# fryza-mied.net
KiCad netlist of a schematic drawn in EAGLE
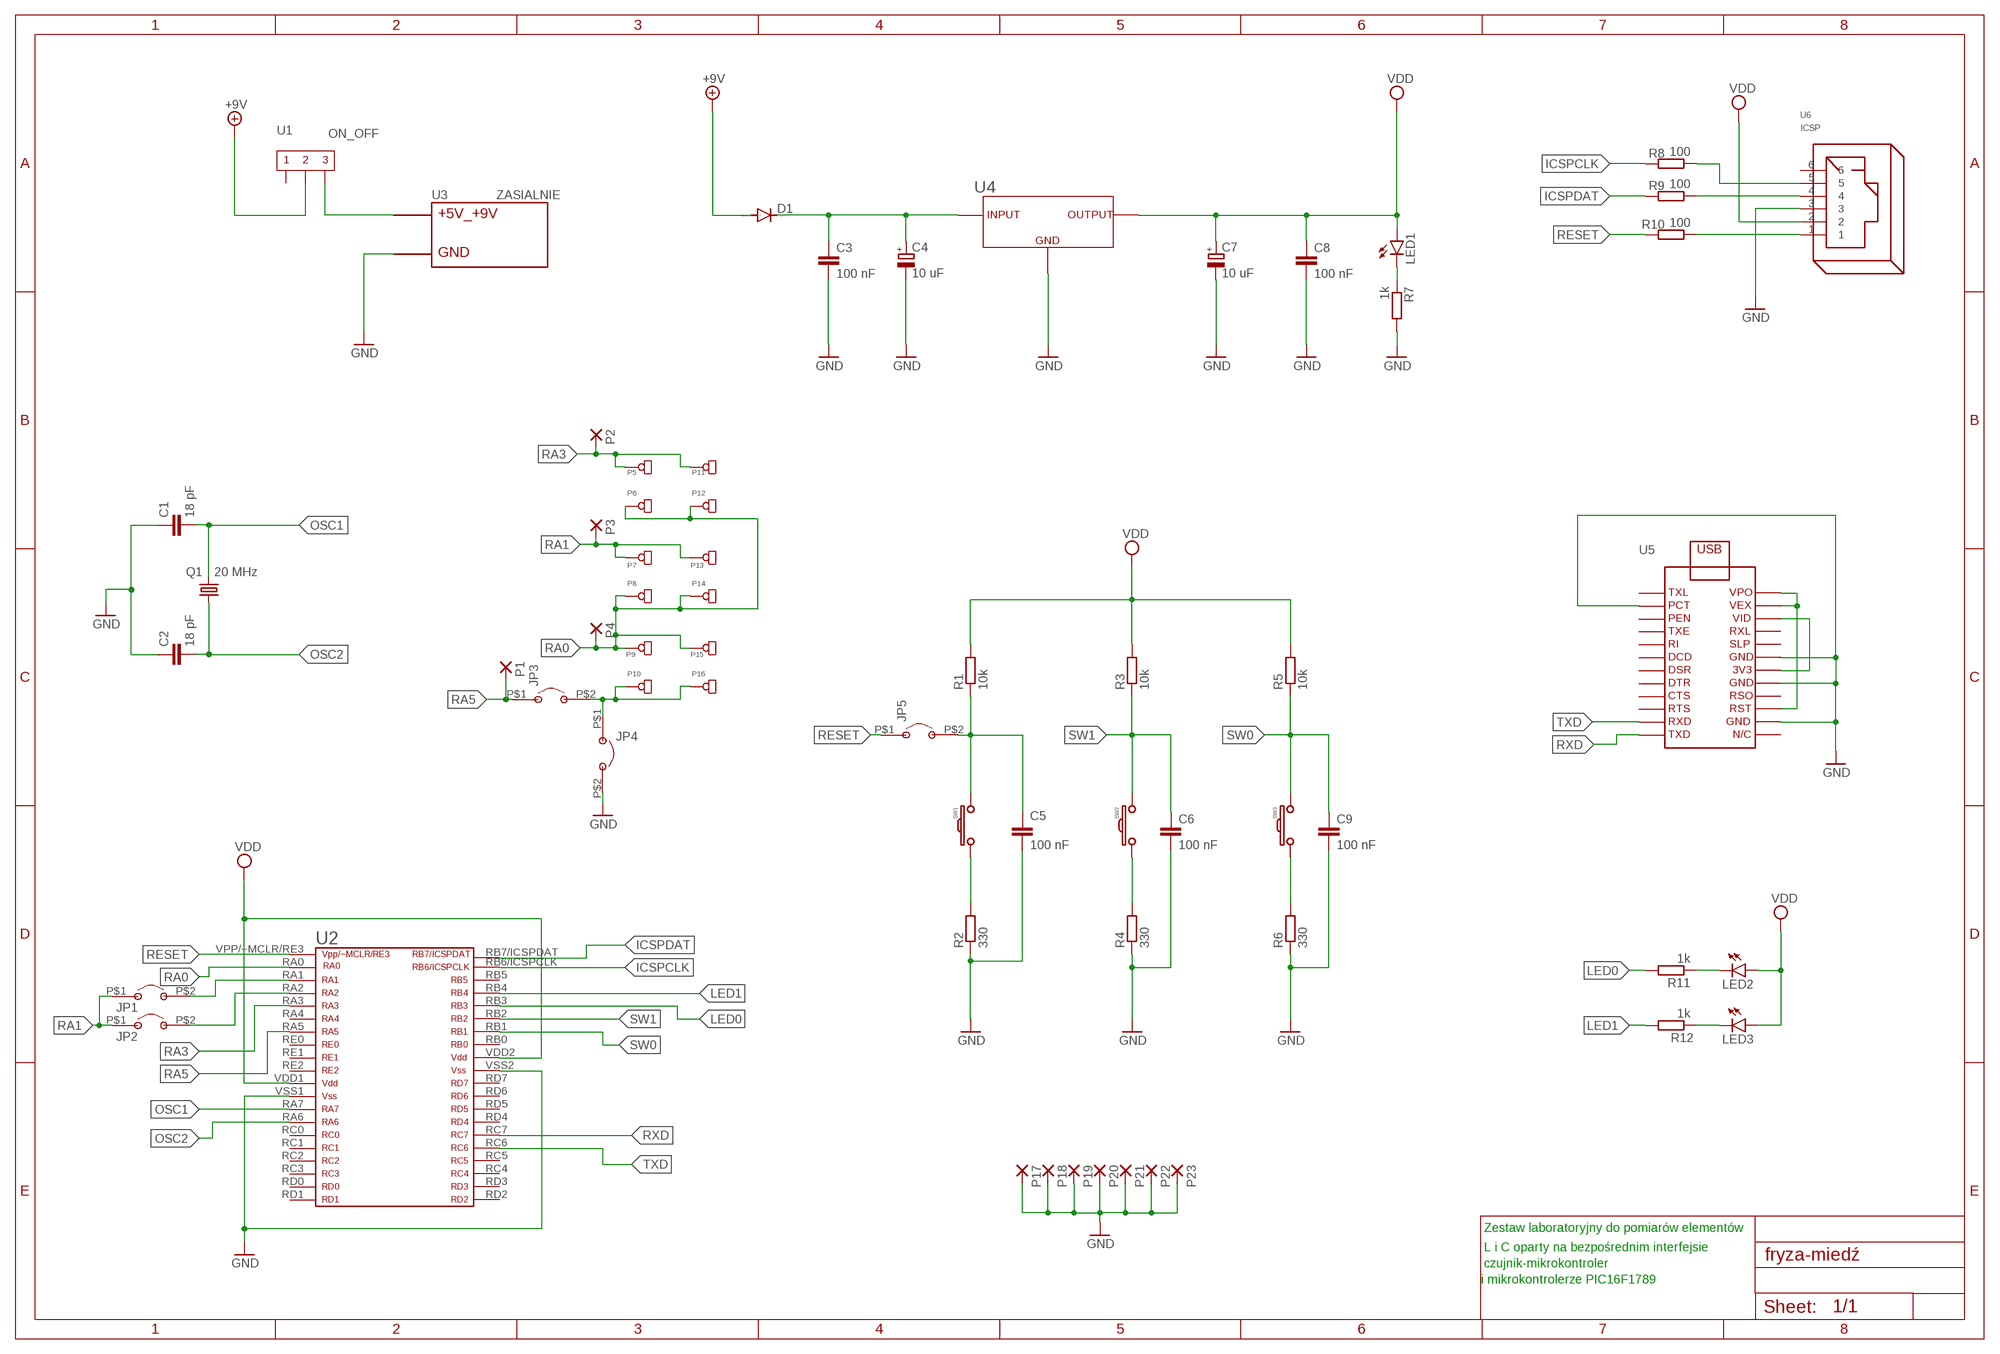
[diagram p0: schematic, sheet 1]

(export (version "E")
  (design (tool "Eeschema 10.0.6"))
  (components
    (comp (ref "C1")
      (value "18 pF")
      (footprint "eagle-import:C050-035X075")
      (libsource (lib "eagle-import") (part "C-EU050-035X075"))
    )
    (comp (ref "C2")
      (value "18 pF")
      (footprint "eagle-import:C050-035X075")
      (libsource (lib "eagle-import") (part "C-EU050-035X075"))
    )
    (comp (ref "C3")
      (value "100 nF")
      (footprint "eagle-import:C050-035X075")
      (libsource (lib "eagle-import") (part "C-EU050-035X075"))
    )
    (comp (ref "C4")
      (value "10 uF")
      (footprint "eagle-import:E2,5-5")
      (libsource (lib "eagle-import") (part "CPOL-EUE2.5-5"))
    )
    (comp (ref "C5")
      (value "100 nF")
      (footprint "eagle-import:C050-035X075")
      (libsource (lib "eagle-import") (part "C-EU050-035X075"))
    )
    (comp (ref "C6")
      (value "100 nF")
      (footprint "eagle-import:C050-035X075")
      (libsource (lib "eagle-import") (part "C-EU050-035X075"))
    )
    (comp (ref "C7")
      (value "10 uF")
      (footprint "eagle-import:E2,5-5")
      (libsource (lib "eagle-import") (part "CPOL-EUE2.5-5"))
    )
    (comp (ref "C8")
      (value "100 nF")
      (footprint "eagle-import:C050-035X075")
      (libsource (lib "eagle-import") (part "C-EU050-035X075"))
    )
    (comp (ref "C9")
      (value "100 nF")
      (footprint "eagle-import:C050-035X075")
      (libsource (lib "eagle-import") (part "C-EU050-035X075"))
    )
    (comp (ref "D1")
      (value "1N4004")
      (footprint "eagle-import:DO41-10")
      (libsource (lib "eagle-import") (part "1N4004"))
    )
    (comp (ref "JP1")
      (value "JUMPER")
      (footprint "eagle-import:JUMPER")
      (libsource (lib "eagle-import") (part "JUMPER"))
    )
    (comp (ref "JP2")
      (value "JUMPER")
      (footprint "eagle-import:JUMPER")
      (libsource (lib "eagle-import") (part "JUMPER"))
    )
    (comp (ref "JP3")
      (value "JUMPER")
      (footprint "eagle-import:JUMPER")
      (libsource (lib "eagle-import") (part "JUMPER"))
    )
    (comp (ref "JP4")
      (value "JUMPER")
      (footprint "eagle-import:JUMPER")
      (libsource (lib "eagle-import") (part "JUMPER"))
    )
    (comp (ref "JP5")
      (value "JUMPER")
      (footprint "eagle-import:JUMPER")
      (libsource (lib "eagle-import") (part "JUMPER"))
    )
    (comp (ref "LED1")
      (value "LED5MM")
      (footprint "eagle-import:LED5MM")
      (libsource (lib "eagle-import") (part "LED5MM"))
    )
    (comp (ref "LED2")
      (value "LED5MM")
      (footprint "eagle-import:LED5MM")
      (libsource (lib "eagle-import") (part "LED5MM"))
    )
    (comp (ref "LED3")
      (value "LED5MM")
      (footprint "eagle-import:LED5MM")
      (libsource (lib "eagle-import") (part "LED5MM"))
    )
    (comp (ref "P1")
      (value "SZPILKA")
      (footprint "eagle-import:CON")
      (libsource (lib "eagle-import") (part "SZPILKA"))
    )
    (comp (ref "P2")
      (value "SZPILKA")
      (footprint "eagle-import:CON")
      (libsource (lib "eagle-import") (part "SZPILKA"))
    )
    (comp (ref "P3")
      (value "SZPILKA")
      (footprint "eagle-import:CON")
      (libsource (lib "eagle-import") (part "SZPILKA"))
    )
    (comp (ref "P4")
      (value "SZPILKA")
      (footprint "eagle-import:CON")
      (libsource (lib "eagle-import") (part "SZPILKA"))
    )
    (comp (ref "P5")
      (value "CON")
      (footprint "eagle-import:CON")
      (libsource (lib "eagle-import") (part "CON"))
    )
    (comp (ref "P6")
      (value "CON")
      (footprint "eagle-import:CON")
      (libsource (lib "eagle-import") (part "CON"))
    )
    (comp (ref "P7")
      (value "CON")
      (footprint "eagle-import:CON")
      (libsource (lib "eagle-import") (part "CON"))
    )
    (comp (ref "P8")
      (value "CON")
      (footprint "eagle-import:CON")
      (libsource (lib "eagle-import") (part "CON"))
    )
    (comp (ref "P9")
      (value "CON")
      (footprint "eagle-import:CON")
      (libsource (lib "eagle-import") (part "CON"))
    )
    (comp (ref "P10")
      (value "CON")
      (footprint "eagle-import:CON")
      (libsource (lib "eagle-import") (part "CON"))
    )
    (comp (ref "P11")
      (value "CON")
      (footprint "eagle-import:CON")
      (libsource (lib "eagle-import") (part "CON"))
    )
    (comp (ref "P12")
      (value "CON")
      (footprint "eagle-import:CON")
      (libsource (lib "eagle-import") (part "CON"))
    )
    (comp (ref "P13")
      (value "CON")
      (footprint "eagle-import:CON")
      (libsource (lib "eagle-import") (part "CON"))
    )
    (comp (ref "P14")
      (value "CON")
      (footprint "eagle-import:CON")
      (libsource (lib "eagle-import") (part "CON"))
    )
    (comp (ref "P15")
      (value "CON")
      (footprint "eagle-import:CON")
      (libsource (lib "eagle-import") (part "CON"))
    )
    (comp (ref "P16")
      (value "CON")
      (footprint "eagle-import:CON")
      (libsource (lib "eagle-import") (part "CON"))
    )
    (comp (ref "P17")
      (value "SZPILKA")
      (footprint "eagle-import:CON")
      (libsource (lib "eagle-import") (part "SZPILKA"))
    )
    (comp (ref "P18")
      (value "SZPILKA")
      (footprint "eagle-import:CON")
      (libsource (lib "eagle-import") (part "SZPILKA"))
    )
    (comp (ref "P19")
      (value "SZPILKA")
      (footprint "eagle-import:CON")
      (libsource (lib "eagle-import") (part "SZPILKA"))
    )
    (comp (ref "P20")
      (value "SZPILKA")
      (footprint "eagle-import:CON")
      (libsource (lib "eagle-import") (part "SZPILKA"))
    )
    (comp (ref "P21")
      (value "SZPILKA")
      (footprint "eagle-import:CON")
      (libsource (lib "eagle-import") (part "SZPILKA"))
    )
    (comp (ref "P22")
      (value "SZPILKA")
      (footprint "eagle-import:CON")
      (libsource (lib "eagle-import") (part "SZPILKA"))
    )
    (comp (ref "P23")
      (value "SZPILKA")
      (footprint "eagle-import:CON")
      (libsource (lib "eagle-import") (part "SZPILKA"))
    )
    (comp (ref "Q1")
      (value "20 MHz")
      (footprint "eagle-import:KWARC")
      (libsource (lib "eagle-import") (part "KWARC"))
    )
    (comp (ref "R1")
      (value "10k")
      (footprint "eagle-import:0207_10")
      (libsource (lib "eagle-import") (part "R-EU_0207/10"))
    )
    (comp (ref "R2")
      (value "330")
      (footprint "eagle-import:0207_10")
      (libsource (lib "eagle-import") (part "R-EU_0207/10"))
    )
    (comp (ref "R3")
      (value "10k")
      (footprint "eagle-import:0207_10")
      (libsource (lib "eagle-import") (part "R-EU_0207/10"))
    )
    (comp (ref "R4")
      (value "330")
      (footprint "eagle-import:0207_10")
      (libsource (lib "eagle-import") (part "R-EU_0207/10"))
    )
    (comp (ref "R5")
      (value "10k")
      (footprint "eagle-import:0207_10")
      (libsource (lib "eagle-import") (part "R-EU_0207/10"))
    )
    (comp (ref "R6")
      (value "330")
      (footprint "eagle-import:0207_10")
      (libsource (lib "eagle-import") (part "R-EU_0207/10"))
    )
    (comp (ref "R7")
      (value "1k")
      (footprint "eagle-import:0207_10")
      (libsource (lib "eagle-import") (part "R-EU_0207/10"))
    )
    (comp (ref "R8")
      (value "100")
      (footprint "eagle-import:0207_10")
      (libsource (lib "eagle-import") (part "R-EU_0207/10"))
    )
    (comp (ref "R9")
      (value "100")
      (footprint "eagle-import:0207_10")
      (libsource (lib "eagle-import") (part "R-EU_0207/10"))
    )
    (comp (ref "R10")
      (value "100")
      (footprint "eagle-import:0207_10")
      (libsource (lib "eagle-import") (part "R-EU_0207/10"))
    )
    (comp (ref "R11")
      (value "1k")
      (footprint "eagle-import:0207_10")
      (libsource (lib "eagle-import") (part "R-EU_0207/10"))
    )
    (comp (ref "R12")
      (value "1k")
      (footprint "eagle-import:0207_10")
      (libsource (lib "eagle-import") (part "R-EU_0207/10"))
    )
    (comp (ref "SW1")
      (value "PUSH_SWITCH")
      (footprint "eagle-import:PUSH_SWITCH")
      (libsource (lib "eagle-import") (part "PUSH_SWITCH"))
    )
    (comp (ref "SW2")
      (value "PUSH_SWITCH")
      (footprint "eagle-import:PUSH_SWITCH")
      (libsource (lib "eagle-import") (part "PUSH_SWITCH"))
    )
    (comp (ref "SW3")
      (value "PUSH_SWITCH")
      (footprint "eagle-import:PUSH_SWITCH")
      (libsource (lib "eagle-import") (part "PUSH_SWITCH"))
    )
    (comp (ref "U1")
      (value "ON_OFF")
      (footprint "eagle-import:WLACZNIK")
      (libsource (lib "eagle-import") (part "WLACZNIK"))
    )
    (comp (ref "U2")
      (value "PIC16F1789")
      (footprint "eagle-import:PIC16F1789")
      (libsource (lib "eagle-import") (part "PIC16F1789"))
    )
    (comp (ref "U3")
      (value "ZASIALNIE")
      (footprint "eagle-import:ZASILANIE_ZLACZE")
      (libsource (lib "eagle-import") (part "ZASILANIE_ZLACZE"))
    )
    (comp (ref "U4")
      (value "LF33CV")
      (footprint "eagle-import:LF33CV")
      (libsource (lib "eagle-import") (part "LF33CV"))
    )
    (comp (ref "U5")
      (value "MMUSB232")
      (footprint "eagle-import:MMUSB232")
      (libsource (lib "eagle-import") (part "MMUSB232"))
    )
    (comp (ref "U6")
      (value "ICSP")
      (footprint "eagle-import:RJ12")
      (libsource (lib "eagle-import") (part "RJ12"))
    )
  )
  (nets
    (net (code "1") (name "+9V") (class "Default")
      (node (ref "D1") (pin "A") (pinfunction "A_A") (pintype "passive"))
      (node (ref "U1") (pin "2") (pinfunction "2_2") (pintype "bidirectional"))
    )
    (net (code "2") (name "GND") (class "Default")
      (node (ref "C1") (pin "1") (pinfunction "1_1") (pintype "passive"))
      (node (ref "C2") (pin "1") (pinfunction "1_1") (pintype "passive"))
      (node (ref "C3") (pin "2") (pinfunction "2_2") (pintype "passive"))
      (node (ref "C4") (pin "-") (pinfunction "-_-") (pintype "passive"))
      (node (ref "C5") (pin "2") (pinfunction "2_2") (pintype "passive"))
      (node (ref "C6") (pin "2") (pinfunction "2_2") (pintype "passive"))
      (node (ref "C7") (pin "-") (pinfunction "-_-") (pintype "passive"))
      (node (ref "C8") (pin "2") (pinfunction "2_2") (pintype "passive"))
      (node (ref "C9") (pin "2") (pinfunction "2_2") (pintype "passive"))
      (node (ref "JP4") (pin "P$2") (pinfunction "P$2_P$2") (pintype "bidirectional"))
      (node (ref "P17") (pin "P$1") (pinfunction "P_P$1") (pintype "passive"))
      (node (ref "P18") (pin "P$1") (pinfunction "P_P$1") (pintype "passive"))
      (node (ref "P19") (pin "P$1") (pinfunction "P_P$1") (pintype "passive"))
      (node (ref "P20") (pin "P$1") (pinfunction "P_P$1") (pintype "passive"))
      (node (ref "P21") (pin "P$1") (pinfunction "P_P$1") (pintype "passive"))
      (node (ref "P22") (pin "P$1") (pinfunction "P_P$1") (pintype "passive"))
      (node (ref "P23") (pin "P$1") (pinfunction "P_P$1") (pintype "passive"))
      (node (ref "R2") (pin "1") (pinfunction "1_1") (pintype "passive"))
      (node (ref "R4") (pin "1") (pinfunction "1_1") (pintype "passive"))
      (node (ref "R6") (pin "1") (pinfunction "1_1") (pintype "passive"))
      (node (ref "R7") (pin "2") (pinfunction "2_2") (pintype "passive"))
      (node (ref "U2") (pin "VSS1") (pinfunction "VSS1_VSS1") (pintype "bidirectional"))
      (node (ref "U2") (pin "VSS2") (pinfunction "VSS2_VSS2") (pintype "bidirectional"))
      (node (ref "U3") (pin "GND1") (pinfunction "GND_GND1") (pintype "bidirectional"))
      (node (ref "U3") (pin "GND2") (pinfunction "GND_GND2") (pintype "bidirectional"))
      (node (ref "U4") (pin "GND") (pinfunction "GND_GND") (pintype "bidirectional"))
      (node (ref "U5") (pin "GND") (pinfunction "GND_GND") (pintype "bidirectional"))
      (node (ref "U5") (pin "GND1") (pinfunction "GND1_GND1") (pintype "bidirectional"))
      (node (ref "U5") (pin "GND2") (pinfunction "GND2_GND2") (pintype "bidirectional"))
      (node (ref "U5") (pin "PCT") (pinfunction "PCT_PCT") (pintype "bidirectional"))
      (node (ref "U6") (pin "3") (pinfunction "3_3") (pintype "bidirectional"))
    )
    (net (code "3") (name "ICSPCLK") (class "Default")
      (node (ref "R8") (pin "2") (pinfunction "2_2") (pintype "passive"))
      (node (ref "U2") (pin "RB6/ICSPCLK") (pinfunction "RB6/ICSPCLK_RB6/ICSPCLK") (pintype "bidirectional"))
    )
    (net (code "4") (name "ICSPDAT") (class "Default")
      (node (ref "R9") (pin "2") (pinfunction "2_2") (pintype "passive"))
      (node (ref "U2") (pin "RB7/ICSPDAT") (pinfunction "RB7/ICSPDAT_RB7/ICSPDAT") (pintype "bidirectional"))
    )
    (net (code "5") (name "LED0") (class "Default")
      (node (ref "R11") (pin "2") (pinfunction "2_2") (pintype "passive"))
      (node (ref "U2") (pin "RB3") (pinfunction "RB3_RB3") (pintype "bidirectional"))
    )
    (net (code "6") (name "LED1") (class "Default")
      (node (ref "R12") (pin "2") (pinfunction "2_2") (pintype "passive"))
      (node (ref "U2") (pin "RB4") (pinfunction "RB4_RB4") (pintype "bidirectional"))
    )
    (net (code "7") (name "Net-(C3-Pad1)") (class "Default")
      (node (ref "C3") (pin "1") (pinfunction "1_1") (pintype "passive"))
      (node (ref "C4") (pin "+") (pinfunction "+_+") (pintype "passive"))
      (node (ref "D1") (pin "C") (pinfunction "C_C") (pintype "passive"))
      (node (ref "U4") (pin "INPUT") (pinfunction "INPUT_INPUT") (pintype "bidirectional"))
    )
    (net (code "8") (name "Net-(C5-Pad1)") (class "Default")
      (node (ref "C5") (pin "1") (pinfunction "1_1") (pintype "passive"))
      (node (ref "JP5") (pin "P$2") (pinfunction "P$2_P$2") (pintype "bidirectional"))
      (node (ref "R1") (pin "1") (pinfunction "1_1") (pintype "passive"))
      (node (ref "SW1") (pin "1_1") (pinfunction "P$1_1_1") (pintype "bidirectional"))
      (node (ref "SW1") (pin "1_2") (pinfunction "P$1_1_2") (pintype "bidirectional"))
    )
    (net (code "9") (name "Net-(JP1-PadP$2)") (class "Default")
      (node (ref "JP1") (pin "P$2") (pinfunction "P$2_P$2") (pintype "bidirectional"))
      (node (ref "U2") (pin "RA1") (pinfunction "RA1_RA1") (pintype "bidirectional"))
    )
    (net (code "10") (name "Net-(JP2-PadP$2)") (class "Default")
      (node (ref "JP2") (pin "P$2") (pinfunction "P$2_P$2") (pintype "bidirectional"))
      (node (ref "U2") (pin "RA2") (pinfunction "RA2_RA2") (pintype "bidirectional"))
    )
    (net (code "11") (name "Net-(LED1-C)") (class "Default")
      (node (ref "LED1") (pin "K") (pinfunction "C_K") (pintype "passive"))
      (node (ref "R7") (pin "1") (pinfunction "1_1") (pintype "passive"))
    )
    (net (code "12") (name "Net-(LED2-C)") (class "Default")
      (node (ref "LED2") (pin "K") (pinfunction "C_K") (pintype "passive"))
      (node (ref "R11") (pin "1") (pinfunction "1_1") (pintype "passive"))
    )
    (net (code "13") (name "Net-(LED3-C)") (class "Default")
      (node (ref "LED3") (pin "K") (pinfunction "C_K") (pintype "passive"))
      (node (ref "R12") (pin "1") (pinfunction "1_1") (pintype "passive"))
    )
    (net (code "14") (name "Net-(P10-P$21)") (class "Default")
      (node (ref "JP3") (pin "P$2") (pinfunction "P$2_P$2") (pintype "bidirectional"))
      (node (ref "JP4") (pin "P$1") (pinfunction "P$1_P$1") (pintype "bidirectional"))
      (node (ref "P10") (pin "P$1") (pinfunction "P$21_P$1") (pintype "bidirectional"))
      (node (ref "P16") (pin "P$1") (pinfunction "P$21_P$1") (pintype "bidirectional"))
    )
    (net (code "15") (name "Net-(R2-Pad2)") (class "Default")
      (node (ref "R2") (pin "2") (pinfunction "2_2") (pintype "passive"))
      (node (ref "SW1") (pin "2_1") (pinfunction "P$2_2_1") (pintype "bidirectional"))
      (node (ref "SW1") (pin "2_2") (pinfunction "P$2_2_2") (pintype "bidirectional"))
    )
    (net (code "16") (name "Net-(R4-Pad2)") (class "Default")
      (node (ref "R4") (pin "2") (pinfunction "2_2") (pintype "passive"))
      (node (ref "SW2") (pin "2_1") (pinfunction "P$2_2_1") (pintype "bidirectional"))
      (node (ref "SW2") (pin "2_2") (pinfunction "P$2_2_2") (pintype "bidirectional"))
    )
    (net (code "17") (name "Net-(R6-Pad2)") (class "Default")
      (node (ref "R6") (pin "2") (pinfunction "2_2") (pintype "passive"))
      (node (ref "SW3") (pin "2_1") (pinfunction "P$2_2_1") (pintype "bidirectional"))
      (node (ref "SW3") (pin "2_2") (pinfunction "P$2_2_2") (pintype "bidirectional"))
    )
    (net (code "18") (name "Net-(R8-Pad1)") (class "Default")
      (node (ref "R8") (pin "1") (pinfunction "1_1") (pintype "passive"))
      (node (ref "U6") (pin "5") (pinfunction "5_5") (pintype "bidirectional"))
    )
    (net (code "19") (name "Net-(R9-Pad1)") (class "Default")
      (node (ref "R9") (pin "1") (pinfunction "1_1") (pintype "passive"))
      (node (ref "U6") (pin "4") (pinfunction "4_4") (pintype "bidirectional"))
    )
    (net (code "20") (name "Net-(R10-Pad1)") (class "Default")
      (node (ref "R10") (pin "1") (pinfunction "1_1") (pintype "passive"))
      (node (ref "U6") (pin "1") (pinfunction "1_1") (pintype "bidirectional"))
    )
    (net (code "21") (name "Net-(U3-+5V_+9V)") (class "Default")
      (node (ref "U1") (pin "3") (pinfunction "3_3") (pintype "bidirectional"))
      (node (ref "U3") (pin "V_S") (pinfunction "+5V_+9V_V_S") (pintype "bidirectional"))
    )
    (net (code "22") (name "Net-(U5-PadRST)") (class "Default")
      (node (ref "U5") (pin "RST") (pinfunction "RST_RST") (pintype "bidirectional"))
      (node (ref "U5") (pin "VEX") (pinfunction "VEX_VEX") (pintype "bidirectional"))
      (node (ref "U5") (pin "VPO") (pinfunction "VPO_VPO") (pintype "bidirectional"))
    )
    (net (code "23") (name "Net-(U5-VID)") (class "Default")
      (node (ref "U5") (pin "3V3") (pinfunction "3V3_3V3") (pintype "bidirectional"))
      (node (ref "U5") (pin "VIO") (pinfunction "VID_VIO") (pintype "bidirectional"))
    )
    (net (code "24") (name "OSC1") (class "Default")
      (node (ref "C1") (pin "2") (pinfunction "2_2") (pintype "passive"))
      (node (ref "Q1") (pin "P$2") (pinfunction "2_P$2") (pintype "passive"))
      (node (ref "U2") (pin "RA7") (pinfunction "RA7_RA7") (pintype "bidirectional"))
    )
    (net (code "25") (name "OSC2") (class "Default")
      (node (ref "C2") (pin "2") (pinfunction "2_2") (pintype "passive"))
      (node (ref "Q1") (pin "P$1") (pinfunction "1_P$1") (pintype "passive"))
      (node (ref "U2") (pin "RA6") (pinfunction "RA6_RA6") (pintype "bidirectional"))
    )
    (net (code "26") (name "RA0") (class "Default")
      (node (ref "P12") (pin "P$1") (pinfunction "P$21_P$1") (pintype "bidirectional"))
      (node (ref "P14") (pin "P$1") (pinfunction "P$21_P$1") (pintype "bidirectional"))
      (node (ref "P15") (pin "P$1") (pinfunction "P$21_P$1") (pintype "bidirectional"))
      (node (ref "P4") (pin "P$1") (pinfunction "P_P$1") (pintype "passive"))
      (node (ref "P6") (pin "P$1") (pinfunction "P$21_P$1") (pintype "bidirectional"))
      (node (ref "P8") (pin "P$1") (pinfunction "P$21_P$1") (pintype "bidirectional"))
      (node (ref "P9") (pin "P$1") (pinfunction "P$21_P$1") (pintype "bidirectional"))
      (node (ref "U2") (pin "RA0") (pinfunction "RA0_RA0") (pintype "bidirectional"))
    )
    (net (code "27") (name "RA1") (class "Default")
      (node (ref "JP1") (pin "P$1") (pinfunction "P$1_P$1") (pintype "bidirectional"))
      (node (ref "JP2") (pin "P$1") (pinfunction "P$1_P$1") (pintype "bidirectional"))
      (node (ref "P13") (pin "P$1") (pinfunction "P$21_P$1") (pintype "bidirectional"))
      (node (ref "P3") (pin "P$1") (pinfunction "P_P$1") (pintype "passive"))
      (node (ref "P7") (pin "P$1") (pinfunction "P$21_P$1") (pintype "bidirectional"))
    )
    (net (code "28") (name "RA3") (class "Default")
      (node (ref "P11") (pin "P$1") (pinfunction "P$21_P$1") (pintype "bidirectional"))
      (node (ref "P2") (pin "P$1") (pinfunction "P_P$1") (pintype "passive"))
      (node (ref "P5") (pin "P$1") (pinfunction "P$21_P$1") (pintype "bidirectional"))
      (node (ref "U2") (pin "RA3") (pinfunction "RA3_RA3") (pintype "bidirectional"))
    )
    (net (code "29") (name "RA5") (class "Default")
      (node (ref "JP3") (pin "P$1") (pinfunction "P$1_P$1") (pintype "bidirectional"))
      (node (ref "P1") (pin "P$1") (pinfunction "P_P$1") (pintype "passive"))
      (node (ref "U2") (pin "RA5") (pinfunction "RA5_RA5") (pintype "bidirectional"))
    )
    (net (code "30") (name "RESET") (class "Default")
      (node (ref "JP5") (pin "P$1") (pinfunction "P$1_P$1") (pintype "bidirectional"))
      (node (ref "R10") (pin "2") (pinfunction "2_2") (pintype "passive"))
      (node (ref "U2") (pin "VPP/~MCLR/RE3") (pinfunction "VPP/~{MCLR/RE3}_VPP/~MCLR/RE3") (pintype "bidirectional"))
    )
    (net (code "31") (name "RXD") (class "Default")
      (node (ref "U2") (pin "RC7") (pinfunction "RC7_RC7") (pintype "bidirectional"))
      (node (ref "U5") (pin "TXD") (pinfunction "TXD_TXD") (pintype "bidirectional"))
    )
    (net (code "32") (name "SW0") (class "Default")
      (node (ref "C9") (pin "1") (pinfunction "1_1") (pintype "passive"))
      (node (ref "R5") (pin "1") (pinfunction "1_1") (pintype "passive"))
      (node (ref "SW3") (pin "1_1") (pinfunction "P$1_1_1") (pintype "bidirectional"))
      (node (ref "SW3") (pin "1_2") (pinfunction "P$1_1_2") (pintype "bidirectional"))
      (node (ref "U2") (pin "RB1") (pinfunction "RB1_RB1") (pintype "bidirectional"))
    )
    (net (code "33") (name "SW1") (class "Default")
      (node (ref "C6") (pin "1") (pinfunction "1_1") (pintype "passive"))
      (node (ref "R3") (pin "1") (pinfunction "1_1") (pintype "passive"))
      (node (ref "SW2") (pin "1_1") (pinfunction "P$1_1_1") (pintype "bidirectional"))
      (node (ref "SW2") (pin "1_2") (pinfunction "P$1_1_2") (pintype "bidirectional"))
      (node (ref "U2") (pin "RB2") (pinfunction "RB2_RB2") (pintype "bidirectional"))
    )
    (net (code "34") (name "TXD") (class "Default")
      (node (ref "U2") (pin "RC6") (pinfunction "RC6_RC6") (pintype "bidirectional"))
      (node (ref "U5") (pin "RXD") (pinfunction "RXD_RXD") (pintype "bidirectional"))
    )
    (net (code "35") (name "VDD") (class "Default")
      (node (ref "C7") (pin "+") (pinfunction "+_+") (pintype "passive"))
      (node (ref "C8") (pin "1") (pinfunction "1_1") (pintype "passive"))
      (node (ref "LED1") (pin "A") (pinfunction "A_A") (pintype "passive"))
      (node (ref "LED2") (pin "A") (pinfunction "A_A") (pintype "passive"))
      (node (ref "LED3") (pin "A") (pinfunction "A_A") (pintype "passive"))
      (node (ref "R1") (pin "2") (pinfunction "2_2") (pintype "passive"))
      (node (ref "R3") (pin "2") (pinfunction "2_2") (pintype "passive"))
      (node (ref "R5") (pin "2") (pinfunction "2_2") (pintype "passive"))
      (node (ref "U2") (pin "VDD1") (pinfunction "VDD1_VDD1") (pintype "bidirectional"))
      (node (ref "U2") (pin "VDD2") (pinfunction "VDD2_VDD2") (pintype "bidirectional"))
      (node (ref "U4") (pin "OUTPUT") (pinfunction "OUTPUT_OUTPUT") (pintype "bidirectional"))
      (node (ref "U6") (pin "2") (pinfunction "2_2") (pintype "bidirectional"))
    )
    (net (code "36") (name "unconnected-(U1-Pad1)") (class "Default")
      (node (ref "U1") (pin "1") (pinfunction "1_1") (pintype "bidirectional"))
    )
    (net (code "37") (name "unconnected-(U2-PadRA4)") (class "Default")
      (node (ref "U2") (pin "RA4") (pinfunction "RA4_RA4") (pintype "bidirectional"))
    )
    (net (code "38") (name "unconnected-(U2-PadRB0)") (class "Default")
      (node (ref "U2") (pin "RB0") (pinfunction "RB0_RB0") (pintype "bidirectional"))
    )
    (net (code "39") (name "unconnected-(U2-PadRB5)") (class "Default")
      (node (ref "U2") (pin "RB5") (pinfunction "RB5_RB5") (pintype "bidirectional"))
    )
    (net (code "40") (name "unconnected-(U2-PadRC0)") (class "Default")
      (node (ref "U2") (pin "RC0") (pinfunction "RC0_RC0") (pintype "bidirectional"))
    )
    (net (code "41") (name "unconnected-(U2-PadRC1)") (class "Default")
      (node (ref "U2") (pin "RC1") (pinfunction "RC1_RC1") (pintype "bidirectional"))
    )
    (net (code "42") (name "unconnected-(U2-PadRC2)") (class "Default")
      (node (ref "U2") (pin "RC2") (pinfunction "RC2_RC2") (pintype "bidirectional"))
    )
    (net (code "43") (name "unconnected-(U2-PadRC3)") (class "Default")
      (node (ref "U2") (pin "RC3") (pinfunction "RC3_RC3") (pintype "bidirectional"))
    )
    (net (code "44") (name "unconnected-(U2-PadRC4)") (class "Default")
      (node (ref "U2") (pin "RC4") (pinfunction "RC4_RC4") (pintype "bidirectional"))
    )
    (net (code "45") (name "unconnected-(U2-PadRC5)") (class "Default")
      (node (ref "U2") (pin "RC5") (pinfunction "RC5_RC5") (pintype "bidirectional"))
    )
    (net (code "46") (name "unconnected-(U2-PadRD0)") (class "Default")
      (node (ref "U2") (pin "RD0") (pinfunction "RD0_RD0") (pintype "bidirectional"))
    )
    (net (code "47") (name "unconnected-(U2-PadRD1)") (class "Default")
      (node (ref "U2") (pin "RD1") (pinfunction "RD1_RD1") (pintype "bidirectional"))
    )
    (net (code "48") (name "unconnected-(U2-PadRD2)") (class "Default")
      (node (ref "U2") (pin "RD2") (pinfunction "RD2_RD2") (pintype "bidirectional"))
    )
    (net (code "49") (name "unconnected-(U2-PadRD3)") (class "Default")
      (node (ref "U2") (pin "RD3") (pinfunction "RD3_RD3") (pintype "bidirectional"))
    )
    (net (code "50") (name "unconnected-(U2-PadRD4)") (class "Default")
      (node (ref "U2") (pin "RD4") (pinfunction "RD4_RD4") (pintype "bidirectional"))
    )
    (net (code "51") (name "unconnected-(U2-PadRD5)") (class "Default")
      (node (ref "U2") (pin "RD5") (pinfunction "RD5_RD5") (pintype "bidirectional"))
    )
    (net (code "52") (name "unconnected-(U2-PadRD6)") (class "Default")
      (node (ref "U2") (pin "RD6") (pinfunction "RD6_RD6") (pintype "bidirectional"))
    )
    (net (code "53") (name "unconnected-(U2-PadRD7)") (class "Default")
      (node (ref "U2") (pin "RD7") (pinfunction "RD7_RD7") (pintype "bidirectional"))
    )
    (net (code "54") (name "unconnected-(U2-PadRE0)") (class "Default")
      (node (ref "U2") (pin "RE0") (pinfunction "RE0_RE0") (pintype "bidirectional"))
    )
    (net (code "55") (name "unconnected-(U2-PadRE1)") (class "Default")
      (node (ref "U2") (pin "RE1") (pinfunction "RE1_RE1") (pintype "bidirectional"))
    )
    (net (code "56") (name "unconnected-(U2-PadRE2)") (class "Default")
      (node (ref "U2") (pin "RE2") (pinfunction "RE2_RE2") (pintype "bidirectional"))
    )
    (net (code "57") (name "unconnected-(U5-PadCTS)") (class "Default")
      (node (ref "U5") (pin "CTS") (pinfunction "CTS_CTS") (pintype "bidirectional"))
    )
    (net (code "58") (name "unconnected-(U5-PadDCD)") (class "Default")
      (node (ref "U5") (pin "DCD") (pinfunction "DCD_DCD") (pintype "bidirectional"))
    )
    (net (code "59") (name "unconnected-(U5-PadDSR)") (class "Default")
      (node (ref "U5") (pin "DSR") (pinfunction "DSR_DSR") (pintype "bidirectional"))
    )
    (net (code "60") (name "unconnected-(U5-PadDTR)") (class "Default")
      (node (ref "U5") (pin "DTR") (pinfunction "DTR_DTR") (pintype "bidirectional"))
    )
    (net (code "61") (name "unconnected-(U5-PadN{slash}C)") (class "Default")
      (node (ref "U5") (pin "N/C") (pinfunction "N/C_N/C") (pintype "bidirectional"))
    )
    (net (code "62") (name "unconnected-(U5-PadPEN)") (class "Default")
      (node (ref "U5") (pin "PEN") (pinfunction "PEN_PEN") (pintype "bidirectional"))
    )
    (net (code "63") (name "unconnected-(U5-PadRI)") (class "Default")
      (node (ref "U5") (pin "RI") (pinfunction "RI_RI") (pintype "bidirectional"))
    )
    (net (code "64") (name "unconnected-(U5-PadRSO)") (class "Default")
      (node (ref "U5") (pin "RSO") (pinfunction "RSO_RSO") (pintype "bidirectional"))
    )
    (net (code "65") (name "unconnected-(U5-PadRTS)") (class "Default")
      (node (ref "U5") (pin "RTS") (pinfunction "RTS_RTS") (pintype "bidirectional"))
    )
    (net (code "66") (name "unconnected-(U5-PadRXL)") (class "Default")
      (node (ref "U5") (pin "RXL") (pinfunction "RXL_RXL") (pintype "bidirectional"))
    )
    (net (code "67") (name "unconnected-(U5-PadSLP)") (class "Default")
      (node (ref "U5") (pin "SLP") (pinfunction "SLP_SLP") (pintype "bidirectional"))
    )
    (net (code "68") (name "unconnected-(U5-PadTXE)") (class "Default")
      (node (ref "U5") (pin "TXE") (pinfunction "TXE_TXE") (pintype "bidirectional"))
    )
    (net (code "69") (name "unconnected-(U5-PadTXL)") (class "Default")
      (node (ref "U5") (pin "TXL") (pinfunction "TXL_TXL") (pintype "bidirectional"))
    )
    (net (code "70") (name "unconnected-(U6-Pad6)") (class "Default")
      (node (ref "U6") (pin "6") (pinfunction "6_6") (pintype "bidirectional"))
    )
  )
)
